# 8_-DAC_and_MIC.net
KiCad netlist of a schematic drawn in Altium Designer
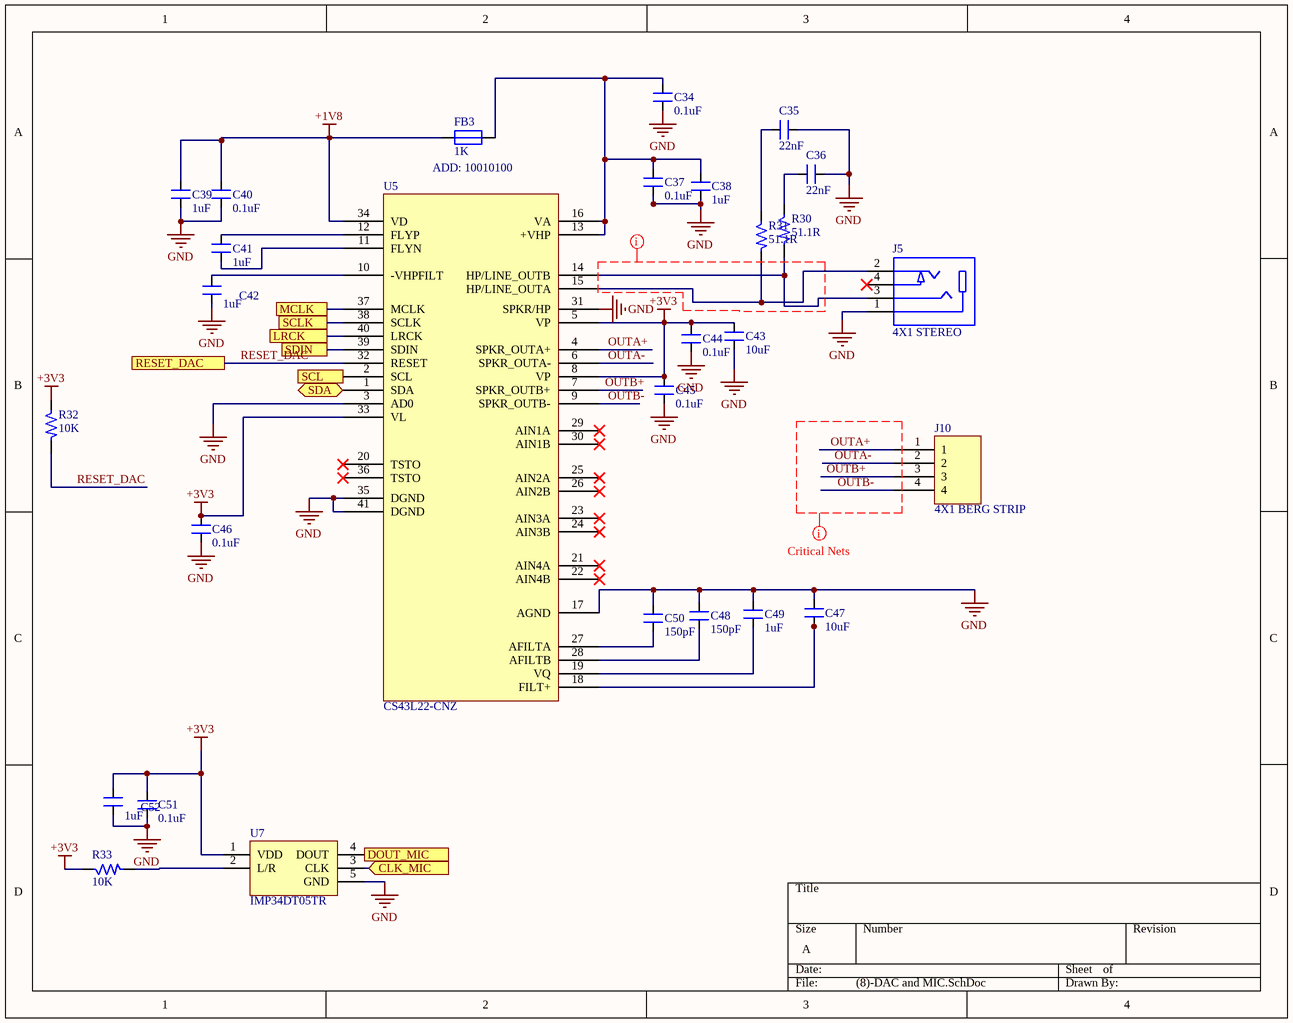
[diagram p0: (8)-DAC and MIC.SchDoc]

(export (version "E")
  (design (tool "Eeschema 10.0.6"))
  (components
    (comp (ref "C34")
      (value "0.1uF")
      (footprint "CAP_0805")
      (description "0.1µF ±10% 50V Ceramic Capacitor X7R 0805 (2012 Metric)")
      (fields
        (field (name "MANUFACTURER") "Samsung")
        (field (name "MANUFACTURER PART NUMBER") "CL21B104KBCNNNC")
      )
      (libsource (lib "ESTEEMPCBLIB") (part "CAP_0.1uF-50V-10%-0805"))
    )
    (comp (ref "C35")
      (value "22nF")
      (footprint "CAP_0805")
      (description "0.022µF ±10% 50V Ceramic Capacitor X7R 0805 (2012 Metric)")
      (fields
        (field (name "MANUFACTURER") "Samsung Electro-Mechanics")
        (field (name "MANUFACTURER PART NUMBER") "CL21B223KBANNNC")
      )
      (libsource (lib "ESTEEMPCBLIB") (part "CAP_22nF-50V-10%-0805"))
    )
    (comp (ref "C36")
      (value "22nF")
      (footprint "CAP_0805")
      (description "0.022µF ±10% 50V Ceramic Capacitor X7R 0805 (2012 Metric)")
      (fields
        (field (name "MANUFACTURER") "Samsung Electro-Mechanics")
        (field (name "MANUFACTURER PART NUMBER") "CL21B223KBANNNC")
      )
      (libsource (lib "ESTEEMPCBLIB") (part "CAP_22nF-50V-10%-0805"))
    )
    (comp (ref "C37")
      (value "0.1uF")
      (footprint "CAP_0805")
      (description "0.1µF ±10% 50V Ceramic Capacitor X7R 0805 (2012 Metric)")
      (fields
        (field (name "MANUFACTURER") "Samsung")
        (field (name "MANUFACTURER PART NUMBER") "CL21B104KBCNNNC")
      )
      (libsource (lib "ESTEEMPCBLIB") (part "CAP_0.1uF-50V-10%-0805"))
    )
    (comp (ref "C38")
      (value "1uF")
      (footprint "CAP_0805")
      (description "1µF ±5% 50V Ceramic Capacitor X7R 0805 (2012 Metric)")
      (fields
        (field (name "MANUFACTURER") "Samsung")
        (field (name "MANUFACTURER PART NUMBER") "CC0805JKX7R9BB105")
      )
      (libsource (lib "ESTEEMPCBLIB") (part "CAP_1uF-50V-5%-0805"))
    )
    (comp (ref "C39")
      (value "1uF")
      (footprint "CAP_0805")
      (description "1µF ±5% 50V Ceramic Capacitor X7R 0805 (2012 Metric)")
      (fields
        (field (name "MANUFACTURER") "Samsung")
        (field (name "MANUFACTURER PART NUMBER") "CC0805JKX7R9BB105")
      )
      (libsource (lib "ESTEEMPCBLIB") (part "CAP_1uF-50V-5%-0805"))
    )
    (comp (ref "C40")
      (value "0.1uF")
      (footprint "CAP_0805")
      (description "0.1µF ±10% 50V Ceramic Capacitor X7R 0805 (2012 Metric)")
      (fields
        (field (name "MANUFACTURER") "Samsung")
        (field (name "MANUFACTURER PART NUMBER") "CL21B104KBCNNNC")
      )
      (libsource (lib "ESTEEMPCBLIB") (part "CAP_0.1uF-50V-10%-0805"))
    )
    (comp (ref "C41")
      (value "1uF")
      (footprint "CAP_0805")
      (description "1µF ±5% 50V Ceramic Capacitor X7R 0805 (2012 Metric)")
      (fields
        (field (name "MANUFACTURER") "Samsung")
        (field (name "MANUFACTURER PART NUMBER") "CC0805JKX7R9BB105")
      )
      (libsource (lib "ESTEEMPCBLIB") (part "CAP_1uF-50V-5%-0805"))
    )
    (comp (ref "C42")
      (value "1uF")
      (footprint "CAP_0805")
      (description "1µF ±5% 50V Ceramic Capacitor X7R 0805 (2012 Metric)")
      (fields
        (field (name "MANUFACTURER") "Samsung")
        (field (name "MANUFACTURER PART NUMBER") "CC0805JKX7R9BB105")
      )
      (libsource (lib "ESTEEMPCBLIB") (part "CAP_1uF-50V-5%-0805"))
    )
    (comp (ref "C43")
      (value "10uF")
      (footprint "CAP_1206")
      (description "10µF ±10% 50V Ceramic Capacitor X7R 1206 (3216 Metric)")
      (fields
        (field (name "MANUFACTURER") "KEMET")
        (field (name "MANUFACTURER PART NUMBER") "CL31B106KBHNNNE")
      )
      (libsource (lib "ESTEEMPCBLIB") (part "CAP_10uF-50V-10%-1206"))
    )
    (comp (ref "C44")
      (value "0.1uF")
      (footprint "CAP_0805")
      (description "0.1µF ±10% 50V Ceramic Capacitor X7R 0805 (2012 Metric)")
      (fields
        (field (name "MANUFACTURER") "Samsung")
        (field (name "MANUFACTURER PART NUMBER") "CL21B104KBCNNNC")
      )
      (libsource (lib "ESTEEMPCBLIB") (part "CAP_0.1uF-50V-10%-0805"))
    )
    (comp (ref "C45")
      (value "0.1uF")
      (footprint "CAP_0805")
      (description "0.1µF ±10% 50V Ceramic Capacitor X7R 0805 (2012 Metric)")
      (fields
        (field (name "MANUFACTURER") "Samsung")
        (field (name "MANUFACTURER PART NUMBER") "CL21B104KBCNNNC")
      )
      (libsource (lib "ESTEEMPCBLIB") (part "CAP_0.1uF-50V-10%-0805"))
    )
    (comp (ref "C46")
      (value "0.1uF")
      (footprint "CAP_0805")
      (description "0.1µF ±10% 50V Ceramic Capacitor X7R 0805 (2012 Metric)")
      (fields
        (field (name "MANUFACTURER") "Samsung")
        (field (name "MANUFACTURER PART NUMBER") "CL21B104KBCNNNC")
      )
      (libsource (lib "ESTEEMPCBLIB") (part "CAP_0.1uF-50V-10%-0805"))
    )
    (comp (ref "C47")
      (value "10uF")
      (footprint "CAP_1206")
      (description "10µF ±10% 50V Ceramic Capacitor X7R 1206 (3216 Metric)")
      (fields
        (field (name "MANUFACTURER") "KEMET")
        (field (name "MANUFACTURER PART NUMBER") "CL31B106KBHNNNE")
      )
      (libsource (lib "ESTEEMPCBLIB") (part "CAP_10uF-50V-10%-1206"))
    )
    (comp (ref "C48")
      (value "150pF")
      (footprint "CAP_0805")
      (description "150pF ±10% 50V Ceramic Capacitor C0G, NP0 0805 (2012 Metric)")
      (fields
        (field (name "MANUFACTURER") "AVX Corporation")
        (field (name "MANUFACTURER PART NUMBER") "08055A151KAT2A")
      )
      (libsource (lib "ESTEEMPCBLIB") (part "CAP_150pF-50V-10%-0805"))
    )
    (comp (ref "C49")
      (value "1uF")
      (footprint "CAP_0805")
      (description "1µF ±5% 50V Ceramic Capacitor X7R 0805 (2012 Metric)")
      (fields
        (field (name "MANUFACTURER") "Samsung")
        (field (name "MANUFACTURER PART NUMBER") "CC0805JKX7R9BB105")
      )
      (libsource (lib "ESTEEMPCBLIB") (part "CAP_1uF-50V-5%-0805"))
    )
    (comp (ref "C50")
      (value "150pF")
      (footprint "CAP_0805")
      (description "150pF ±10% 50V Ceramic Capacitor C0G, NP0 0805 (2012 Metric)")
      (fields
        (field (name "MANUFACTURER") "AVX Corporation")
        (field (name "MANUFACTURER PART NUMBER") "08055A151KAT2A")
      )
      (libsource (lib "ESTEEMPCBLIB") (part "CAP_150pF-50V-10%-0805"))
    )
    (comp (ref "C51")
      (value "0.1uF")
      (footprint "CAP_0805")
      (description "0.1µF ±10% 50V Ceramic Capacitor X7R 0805 (2012 Metric)")
      (fields
        (field (name "MANUFACTURER") "Samsung")
        (field (name "MANUFACTURER PART NUMBER") "CL21B104KBCNNNC")
      )
      (libsource (lib "ESTEEMPCBLIB") (part "CAP_0.1uF-50V-10%-0805"))
    )
    (comp (ref "C52")
      (value "1uF")
      (footprint "CAP_0805")
      (description "1µF ±5% 50V Ceramic Capacitor X7R 0805 (2012 Metric)")
      (fields
        (field (name "MANUFACTURER") "Samsung")
        (field (name "MANUFACTURER PART NUMBER") "CC0805JKX7R9BB105")
      )
      (libsource (lib "ESTEEMPCBLIB") (part "CAP_1uF-50V-5%-0805"))
    )
    (comp (ref "FB3")
      (value "1K")
      (footprint "IND_0805")
      (description "1 kOhms @ 100MHz 1 Power Line Ferrite Bead 0805 (2012 Metric) 1.6A")
      (fields
        (field (name "MANUFACTURER") "Laird")
        (field (name "MANUFACTURER PART NUMBER") "BLM21SP102SH1D")
      )
      (libsource (lib "ESTEEMPCBLIB") (part "FB_1K-100MHZ-1.6A-0805"))
    )
    (comp (ref "J5")
      (value "4X1 STEREO")
      (footprint "CON_SJ-2504A-SMT-TR_SMD")
      (fields
        (field (name "MANUFACTURER") "CUI Devices")
        (field (name "MANUFACTURER PART NUMBER") "SJ-2504A-SMT-TR")
      )
      (libsource (lib "ESTEEMPCBLIB") (part "CON-PLG-STEREO_4X1-100-RA-SMD"))
    )
    (comp (ref "J10")
      (value "4X1 BERG STRIP")
      (footprint "CON4_100_40D72_TH_ST_MALE")
      (description "4 Pins, 1 Row 2.54mm Pitch, Straight bergstrip, Male")
      (fields (field (name "MANUFACTURER") "NA"))
      (libsource (lib "ESTEEMPCBLIB") (part "CON-BS-PLG_4X1-100-ST-TH"))
    )
    (comp (ref "R30")
      (value "51.1R")
      (footprint "RES_0603")
      (description "51.1 Ohms ±1% 0.1W, 1/10W Chip Resistor 0603 (1608 Metric) Thick Film")
      (fields
        (field (name "MANUFACTURER") "Vishay Dale")
        (field (name "MANUFACTURER PART NUMBER") "CRCW060351R1FKEAC")
      )
      (libsource (lib "ESTEEMPCBLIB") (part "RES_51.1R-0.1W-1%-0603"))
    )
    (comp (ref "R31")
      (value "51.1R")
      (footprint "RES_0603")
      (description "51.1 Ohms ±1% 0.1W, 1/10W Chip Resistor 0603 (1608 Metric) Thick Film")
      (fields
        (field (name "MANUFACTURER") "Vishay Dale")
        (field (name "MANUFACTURER PART NUMBER") "CRCW060351R1FKEAC")
      )
      (libsource (lib "ESTEEMPCBLIB") (part "RES_51.1R-0.1W-1%-0603"))
    )
    (comp (ref "R32")
      (value "10K")
      (footprint "RES_0603")
      (description "10 kOhms ±1% 0.1W, 1/10W Chip Resistor 0603 (1608 Metric) Automotive AEC-Q200 Thick Film")
      (fields (field (name "MANUFACTURER") "Walsin") (field (name "MANUFACTURER PART NUMBER") "WR06X1002FTL"))
      (libsource (lib "ESTEEMPCBLIB") (part "RES_10K-0.1W-1%-0603"))
    )
    (comp (ref "R33")
      (value "10K")
      (footprint "RES_0603")
      (description "10 kOhms ±1% 0.1W, 1/10W Chip Resistor 0603 (1608 Metric) Automotive AEC-Q200 Thick Film")
      (fields (field (name "MANUFACTURER") "Walsin") (field (name "MANUFACTURER PART NUMBER") "WR06X1002FTL"))
      (libsource (lib "ESTEEMPCBLIB") (part "RES_10K-0.1W-1%-0603"))
    )
    (comp (ref "U5")
      (value "CS43L22-CNZ")
      (footprint "QFN40_19_284_33X9_SMD")
      (description "Audio D/A Converter ICs Low Power Stereo DAC w/ClassD Spkr Driver")
      (fields (field (name "MANUFACTURER") "Cirrus Logic"))
      (libsource (lib "ESTEEMPCBLIB") (part "IC_CS43L22"))
    )
    (comp (ref "U7")
      (value "IMP34DT05TR")
      (footprint "HCLGA-4_53_137_15X37_SMD")
      (description "MEMS Microphones AUTO & INDUSTRIAL SENSORS")
      (fields (field (name "MANUFACTURER") "STMicroelectronics"))
      (libsource (lib "ESTEEMPCBLIB") (part "IC_IMP34DT05TR"))
    )
  )
  (nets
    (net (code "1") (name "+1V8") (class "Default")
      (node (ref "C39") (pin "1") (pinfunction "1_1") (pintype "passive"))
      (node (ref "C40") (pin "1") (pinfunction "1_1") (pintype "passive"))
      (node (ref "FB3") (pin "1") (pinfunction "1_1") (pintype "passive"))
      (node (ref "U5") (pin "34") (pinfunction "VD_34") (pintype "passive"))
    )
    (net (code "2") (name "+3V3") (class "Default")
      (node (ref "C43") (pin "1") (pinfunction "1_1") (pintype "passive"))
      (node (ref "C44") (pin "1") (pinfunction "1_1") (pintype "passive"))
      (node (ref "C45") (pin "1") (pinfunction "1_1") (pintype "passive"))
      (node (ref "C46") (pin "1") (pinfunction "1_1") (pintype "passive"))
      (node (ref "C51") (pin "1") (pinfunction "1_1") (pintype "passive"))
      (node (ref "C52") (pin "1") (pinfunction "1_1") (pintype "passive"))
      (node (ref "R32") (pin "1") (pinfunction "1_1") (pintype "passive"))
      (node (ref "R33") (pin "1") (pinfunction "1_1") (pintype "passive"))
      (node (ref "U5") (pin "33") (pinfunction "VL_33") (pintype "passive"))
      (node (ref "U5") (pin "5") (pinfunction "VP_5") (pintype "passive"))
      (node (ref "U5") (pin "8") (pinfunction "VP_8") (pintype "passive"))
      (node (ref "U7") (pin "1") (pinfunction "VDD_1") (pintype "passive"))
    )
    (net (code "3") (name "/CLK_MIC") (class "Default")
      (node (ref "U7") (pin "3") (pinfunction "CLK_3") (pintype "passive"))
    )
    (net (code "4") (name "/DOUT_MIC") (class "Default")
      (node (ref "U7") (pin "4") (pinfunction "DOUT_4") (pintype "passive"))
    )
    (net (code "5") (name "/LRCK") (class "Default")
      (node (ref "U5") (pin "40") (pinfunction "LRCK_40") (pintype "passive"))
    )
    (net (code "6") (name "/MCLK") (class "Default")
      (node (ref "U5") (pin "37") (pinfunction "MCLK_37") (pintype "passive"))
    )
    (net (code "7") (name "/OUTA+") (class "Default")
      (node (ref "J10") (pin "1") (pinfunction "1_1") (pintype "passive"))
      (node (ref "U5") (pin "4") (pinfunction "SPKR_OUTA+_4") (pintype "passive"))
    )
    (net (code "8") (name "/OUTA-") (class "Default")
      (node (ref "J10") (pin "2") (pinfunction "2_2") (pintype "passive"))
      (node (ref "U5") (pin "6") (pinfunction "SPKR_OUTA-_6") (pintype "passive"))
    )
    (net (code "9") (name "/OUTB+") (class "Default")
      (node (ref "J10") (pin "3") (pinfunction "3_3") (pintype "passive"))
      (node (ref "U5") (pin "7") (pinfunction "SPKR_OUTB+_7") (pintype "passive"))
    )
    (net (code "10") (name "/OUTB-") (class "Default")
      (node (ref "J10") (pin "4") (pinfunction "4_4") (pintype "passive"))
      (node (ref "U5") (pin "9") (pinfunction "SPKR_OUTB-_9") (pintype "passive"))
    )
    (net (code "11") (name "/RESET_DAC") (class "Default")
      (node (ref "R32") (pin "2") (pinfunction "2_2") (pintype "passive"))
      (node (ref "U5") (pin "32") (pinfunction "RESET_32") (pintype "passive"))
    )
    (net (code "12") (name "/SCL") (class "Default")
      (node (ref "U5") (pin "2") (pinfunction "SCL_2") (pintype "passive"))
    )
    (net (code "13") (name "/SCLK") (class "Default")
      (node (ref "U5") (pin "38") (pinfunction "SCLK_38") (pintype "passive"))
    )
    (net (code "14") (name "/SDA") (class "Default")
      (node (ref "U5") (pin "1") (pinfunction "SDA_1") (pintype "passive"))
    )
    (net (code "15") (name "/SDIN") (class "Default")
      (node (ref "U5") (pin "39") (pinfunction "SDIN_39") (pintype "passive"))
    )
    (net (code "16") (name "GND") (class "Default")
      (node (ref "C34") (pin "2") (pinfunction "2_2") (pintype "passive"))
      (node (ref "C35") (pin "2") (pinfunction "2_2") (pintype "passive"))
      (node (ref "C36") (pin "2") (pinfunction "2_2") (pintype "passive"))
      (node (ref "C37") (pin "2") (pinfunction "2_2") (pintype "passive"))
      (node (ref "C38") (pin "2") (pinfunction "2_2") (pintype "passive"))
      (node (ref "C39") (pin "2") (pinfunction "2_2") (pintype "passive"))
      (node (ref "C40") (pin "2") (pinfunction "2_2") (pintype "passive"))
      (node (ref "C42") (pin "2") (pinfunction "2_2") (pintype "passive"))
      (node (ref "C43") (pin "2") (pinfunction "2_2") (pintype "passive"))
      (node (ref "C44") (pin "2") (pinfunction "2_2") (pintype "passive"))
      (node (ref "C45") (pin "2") (pinfunction "2_2") (pintype "passive"))
      (node (ref "C46") (pin "2") (pinfunction "2_2") (pintype "passive"))
      (node (ref "C47") (pin "1") (pinfunction "1_1") (pintype "passive"))
      (node (ref "C48") (pin "1") (pinfunction "1_1") (pintype "passive"))
      (node (ref "C49") (pin "1") (pinfunction "1_1") (pintype "passive"))
      (node (ref "C50") (pin "1") (pinfunction "1_1") (pintype "passive"))
      (node (ref "C51") (pin "2") (pinfunction "2_2") (pintype "passive"))
      (node (ref "C52") (pin "2") (pinfunction "2_2") (pintype "passive"))
      (node (ref "J5") (pin "1") (pinfunction "1_1") (pintype "passive"))
      (node (ref "U5") (pin "17") (pinfunction "AGND_17") (pintype "passive"))
      (node (ref "U5") (pin "3") (pinfunction "AD0_3") (pintype "passive"))
      (node (ref "U5") (pin "31") (pinfunction "SPKR/HP_31") (pintype "passive"))
      (node (ref "U5") (pin "35") (pinfunction "DGND_35") (pintype "passive"))
      (node (ref "U5") (pin "41") (pinfunction "DGND_41") (pintype "passive"))
      (node (ref "U7") (pin "5") (pinfunction "GND_5") (pintype "passive"))
    )
    (net (code "17") (name "Net-(C35-Pad1)") (class "Default")
      (node (ref "C35") (pin "1") (pinfunction "1_1") (pintype "passive"))
      (node (ref "R31") (pin "1") (pinfunction "1_1") (pintype "passive"))
    )
    (net (code "18") (name "Net-(C36-Pad1)") (class "Default")
      (node (ref "C36") (pin "1") (pinfunction "1_1") (pintype "passive"))
      (node (ref "R30") (pin "1") (pinfunction "1_1") (pintype "passive"))
    )
    (net (code "19") (name "Net-(U5-+VHP)") (class "Default")
      (node (ref "C34") (pin "1") (pinfunction "1_1") (pintype "passive"))
      (node (ref "C37") (pin "1") (pinfunction "1_1") (pintype "passive"))
      (node (ref "C38") (pin "1") (pinfunction "1_1") (pintype "passive"))
      (node (ref "FB3") (pin "2") (pinfunction "2_2") (pintype "passive"))
      (node (ref "U5") (pin "13") (pinfunction "+VHP_13") (pintype "passive"))
      (node (ref "U5") (pin "16") (pinfunction "VA_16") (pintype "passive"))
    )
    (net (code "20") (name "Net-(U5--VHPFILT)") (class "Default")
      (node (ref "C42") (pin "1") (pinfunction "1_1") (pintype "passive"))
      (node (ref "U5") (pin "10") (pinfunction "-VHPFILT_10") (pintype "passive"))
    )
    (net (code "21") (name "Net-(U5-AFILTA)") (class "Default")
      (node (ref "C50") (pin "2") (pinfunction "2_2") (pintype "passive"))
      (node (ref "U5") (pin "27") (pinfunction "AFILTA_27") (pintype "passive"))
    )
    (net (code "22") (name "Net-(U5-AFILTB)") (class "Default")
      (node (ref "C48") (pin "2") (pinfunction "2_2") (pintype "passive"))
      (node (ref "U5") (pin "28") (pinfunction "AFILTB_28") (pintype "passive"))
    )
    (net (code "23") (name "Net-(U5-FILT+)") (class "Default")
      (node (ref "C47") (pin "2") (pinfunction "2_2") (pintype "passive"))
      (node (ref "U5") (pin "18") (pinfunction "FILT+_18") (pintype "passive"))
    )
    (net (code "24") (name "Net-(U5-FLYN)") (class "Default")
      (node (ref "C41") (pin "2") (pinfunction "2_2") (pintype "passive"))
      (node (ref "U5") (pin "11") (pinfunction "FLYN_11") (pintype "passive"))
    )
    (net (code "25") (name "Net-(U5-FLYP)") (class "Default")
      (node (ref "C41") (pin "1") (pinfunction "1_1") (pintype "passive"))
      (node (ref "U5") (pin "12") (pinfunction "FLYP_12") (pintype "passive"))
    )
    (net (code "26") (name "Net-(U5-HP{slash}LINE_OUTA)") (class "Default")
      (node (ref "J5") (pin "2") (pinfunction "2_2") (pintype "passive"))
      (node (ref "R31") (pin "2") (pinfunction "2_2") (pintype "passive"))
      (node (ref "U5") (pin "15") (pinfunction "HP/LINE_OUTA_15") (pintype "passive"))
    )
    (net (code "27") (name "Net-(U5-HP{slash}LINE_OUTB)") (class "Default")
      (node (ref "J5") (pin "3") (pinfunction "3_3") (pintype "passive"))
      (node (ref "R30") (pin "2") (pinfunction "2_2") (pintype "passive"))
      (node (ref "U5") (pin "14") (pinfunction "HP/LINE_OUTB_14") (pintype "passive"))
    )
    (net (code "28") (name "Net-(U5-VQ)") (class "Default")
      (node (ref "C49") (pin "2") (pinfunction "2_2") (pintype "passive"))
      (node (ref "U5") (pin "19") (pinfunction "VQ_19") (pintype "passive"))
    )
    (net (code "29") (name "Net-(U7-L{slash}R)") (class "Default")
      (node (ref "R33") (pin "2") (pinfunction "2_2") (pintype "passive"))
      (node (ref "U7") (pin "2") (pinfunction "L/R_2") (pintype "passive"))
    )
    (net (code "30") (name "unconnected-(J5-Pad4)") (class "Default")
      (node (ref "J5") (pin "4") (pinfunction "4_4") (pintype "passive+no_connect"))
    )
    (net (code "31") (name "unconnected-(U5-AIN1A-Pad29)") (class "Default")
      (node (ref "U5") (pin "29") (pinfunction "AIN1A_29") (pintype "passive+no_connect"))
    )
    (net (code "32") (name "unconnected-(U5-AIN1B-Pad30)") (class "Default")
      (node (ref "U5") (pin "30") (pinfunction "AIN1B_30") (pintype "passive+no_connect"))
    )
    (net (code "33") (name "unconnected-(U5-AIN2A-Pad25)") (class "Default")
      (node (ref "U5") (pin "25") (pinfunction "AIN2A_25") (pintype "passive+no_connect"))
    )
    (net (code "34") (name "unconnected-(U5-AIN2B-Pad26)") (class "Default")
      (node (ref "U5") (pin "26") (pinfunction "AIN2B_26") (pintype "passive+no_connect"))
    )
    (net (code "35") (name "unconnected-(U5-AIN3A-Pad23)") (class "Default")
      (node (ref "U5") (pin "23") (pinfunction "AIN3A_23") (pintype "passive+no_connect"))
    )
    (net (code "36") (name "unconnected-(U5-AIN3B-Pad24)") (class "Default")
      (node (ref "U5") (pin "24") (pinfunction "AIN3B_24") (pintype "passive+no_connect"))
    )
    (net (code "37") (name "unconnected-(U5-AIN4A-Pad21)") (class "Default")
      (node (ref "U5") (pin "21") (pinfunction "AIN4A_21") (pintype "passive+no_connect"))
    )
    (net (code "38") (name "unconnected-(U5-AIN4B-Pad22)") (class "Default")
      (node (ref "U5") (pin "22") (pinfunction "AIN4B_22") (pintype "passive+no_connect"))
    )
    (net (code "39") (name "unconnected-(U5-TSTO-Pad20)") (class "Default")
      (node (ref "U5") (pin "20") (pinfunction "TSTO_20") (pintype "passive+no_connect"))
    )
    (net (code "40") (name "unconnected-(U5-TSTO-Pad36)") (class "Default")
      (node (ref "U5") (pin "36") (pinfunction "TSTO_36") (pintype "passive+no_connect"))
    )
  )
)
